# USBdimmer-control.net
KiCad netlist of a schematic drawn in EAGLE
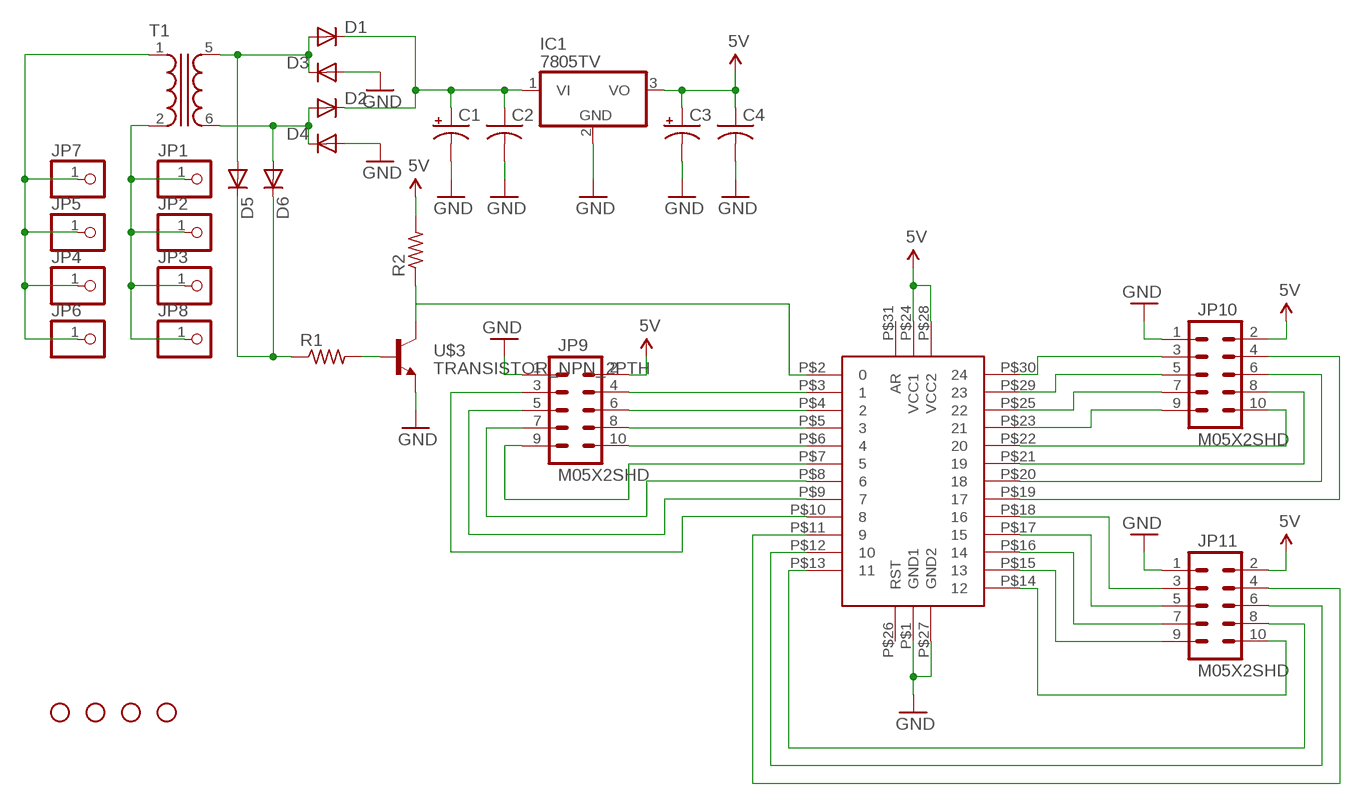
[diagram p0: schematic, sheet 1]

(export (version "E")
  (design (tool "Eeschema 10.0.6"))
  (components
    (comp (ref "C1")
      (value "CPOL-USE3.5-10")
      (footprint "eagle-import:E3,5-10")
      (libsource (lib "eagle-import") (part "CPOL-USE3.5-10"))
    )
    (comp (ref "C2")
      (value "C-US025-030X050")
      (footprint "eagle-import:C025-030X050")
      (libsource (lib "eagle-import") (part "C-US025-030X050"))
    )
    (comp (ref "C3")
      (value "CPOL-USE3.5-10")
      (footprint "eagle-import:E3,5-10")
      (libsource (lib "eagle-import") (part "CPOL-USE3.5-10"))
    )
    (comp (ref "C4")
      (value "C-US025-030X050")
      (footprint "eagle-import:C025-030X050")
      (libsource (lib "eagle-import") (part "C-US025-030X050"))
    )
    (comp (ref "D1")
      (value "DIODEPTH")
      (footprint "eagle-import:DIODE-1N4001")
      (libsource (lib "eagle-import") (part "DIODEPTH"))
    )
    (comp (ref "D2")
      (value "DIODEPTH")
      (footprint "eagle-import:DIODE-1N4001")
      (libsource (lib "eagle-import") (part "DIODEPTH"))
    )
    (comp (ref "D3")
      (value "DIODEPTH")
      (footprint "eagle-import:DIODE-1N4001")
      (libsource (lib "eagle-import") (part "DIODEPTH"))
    )
    (comp (ref "D4")
      (value "DIODEPTH")
      (footprint "eagle-import:DIODE-1N4001")
      (libsource (lib "eagle-import") (part "DIODEPTH"))
    )
    (comp (ref "D5")
      (value "DIODE1N4148")
      (footprint "eagle-import:DIODE-1N4148")
      (libsource (lib "eagle-import") (part "DIODE1N4148"))
    )
    (comp (ref "D6")
      (value "DIODE1N4148")
      (footprint "eagle-import:DIODE-1N4148")
      (libsource (lib "eagle-import") (part "DIODE1N4148"))
    )
    (comp (ref "IC1")
      (value "7805TV")
      (footprint "eagle-import:TO220V")
      (libsource (lib "eagle-import") (part "78TV05"))
    )
    (comp (ref "JP1")
      (value "PINHD-1X1")
      (footprint "eagle-import:1X01")
      (libsource (lib "eagle-import") (part "PINHD-1X1"))
    )
    (comp (ref "JP2")
      (value "PINHD-1X1")
      (footprint "eagle-import:1X01")
      (libsource (lib "eagle-import") (part "PINHD-1X1"))
    )
    (comp (ref "JP3")
      (value "PINHD-1X1")
      (footprint "eagle-import:1X01")
      (libsource (lib "eagle-import") (part "PINHD-1X1"))
    )
    (comp (ref "JP4")
      (value "PINHD-1X1")
      (footprint "eagle-import:1X01")
      (libsource (lib "eagle-import") (part "PINHD-1X1"))
    )
    (comp (ref "JP5")
      (value "PINHD-1X1")
      (footprint "eagle-import:1X01")
      (libsource (lib "eagle-import") (part "PINHD-1X1"))
    )
    (comp (ref "JP6")
      (value "PINHD-1X1")
      (footprint "eagle-import:1X01")
      (libsource (lib "eagle-import") (part "PINHD-1X1"))
    )
    (comp (ref "JP7")
      (value "PINHD-1X1")
      (footprint "eagle-import:1X01")
      (libsource (lib "eagle-import") (part "PINHD-1X1"))
    )
    (comp (ref "JP8")
      (value "PINHD-1X1")
      (footprint "eagle-import:1X01")
      (libsource (lib "eagle-import") (part "PINHD-1X1"))
    )
    (comp (ref "JP9")
      (value "M05X2SHD")
      (footprint "eagle-import:2X5-SHROUDED")
      (libsource (lib "eagle-import") (part "M05X2SHD"))
    )
    (comp (ref "JP10")
      (value "M05X2SHD")
      (footprint "eagle-import:2X5-SHROUDED")
      (libsource (lib "eagle-import") (part "M05X2SHD"))
    )
    (comp (ref "JP11")
      (value "M05X2SHD")
      (footprint "eagle-import:2X5-SHROUDED")
      (libsource (lib "eagle-import") (part "M05X2SHD"))
    )
    (comp (ref "R1")
      (value "FLIPFLOP-RES")
      (footprint "eagle-import:0805-THM")
      (libsource (lib "eagle-import") (part "FLIPFLOP-RES"))
    )
    (comp (ref "R2")
      (value "FLIPFLOP-RES")
      (footprint "eagle-import:0805-THM")
      (libsource (lib "eagle-import") (part "FLIPFLOP-RES"))
    )
    (comp (ref "STANDOFF1")
      (value "STAND-OFF")
      (footprint "eagle-import:STAND-OFF")
      (libsource (lib "eagle-import") (part "STAND-OFF"))
    )
    (comp (ref "STANDOFF2")
      (value "STAND-OFF")
      (footprint "eagle-import:STAND-OFF")
      (libsource (lib "eagle-import") (part "STAND-OFF"))
    )
    (comp (ref "STANDOFF3")
      (value "STAND-OFF")
      (footprint "eagle-import:STAND-OFF")
      (libsource (lib "eagle-import") (part "STAND-OFF"))
    )
    (comp (ref "STANDOFF4")
      (value "STAND-OFF")
      (footprint "eagle-import:STAND-OFF")
      (libsource (lib "eagle-import") (part "STAND-OFF"))
    )
    (comp (ref "T1")
      (value "XFORMER")
      (footprint "eagle-import:T70-E")
      (libsource (lib "eagle-import") (part "XFORMER"))
    )
    (comp (ref "U$1")
      (value "TEENSY2")
      (footprint "eagle-import:TEENSY2")
      (libsource (lib "eagle-import") (part "TEENSY2"))
    )
    (comp (ref "U$3")
      (value "TRANSISTOR_NPN_2PTH")
      (footprint "eagle-import:TO-92")
      (libsource (lib "eagle-import") (part "TRANSISTOR_NPN_2PTH"))
    )
  )
  (nets
    (net (code "1") (name "5V") (class "Default")
      (node (ref "C3") (pin "+") (pinfunction "+_+") (pintype "passive"))
      (node (ref "C4") (pin "1") (pinfunction "1_1") (pintype "passive"))
      (node (ref "IC1") (pin "3") (pinfunction "VO_3") (pintype "passive"))
      (node (ref "JP10") (pin "2") (pinfunction "2_2") (pintype "passive"))
      (node (ref "JP11") (pin "2") (pinfunction "2_2") (pintype "passive"))
      (node (ref "JP9") (pin "2") (pinfunction "2_2") (pintype "passive"))
      (node (ref "R2") (pin "2") (pinfunction "2_2") (pintype "passive"))
      (node (ref "U$1") (pin "P$24") (pinfunction "VCC1_P$24") (pintype "bidirectional"))
      (node (ref "U$1") (pin "P$28") (pinfunction "VCC2_P$28") (pintype "bidirectional"))
    )
    (net (code "2") (name "GND") (class "Default")
      (node (ref "C1") (pin "-") (pinfunction "-_-") (pintype "passive"))
      (node (ref "C2") (pin "2") (pinfunction "2_2") (pintype "passive"))
      (node (ref "C3") (pin "-") (pinfunction "-_-") (pintype "passive"))
      (node (ref "C4") (pin "2") (pinfunction "2_2") (pintype "passive"))
      (node (ref "D3") (pin "A") (pinfunction "A_A") (pintype "passive"))
      (node (ref "D4") (pin "A") (pinfunction "A_A") (pintype "passive"))
      (node (ref "IC1") (pin "2") (pinfunction "GND_2") (pintype "passive"))
      (node (ref "JP10") (pin "1") (pinfunction "1_1") (pintype "passive"))
      (node (ref "JP11") (pin "1") (pinfunction "1_1") (pintype "passive"))
      (node (ref "JP9") (pin "1") (pinfunction "1_1") (pintype "passive"))
      (node (ref "U$1") (pin "P$1") (pinfunction "GND1_P$1") (pintype "bidirectional"))
      (node (ref "U$1") (pin "P$27") (pinfunction "GND2_P$27") (pintype "bidirectional"))
      (node (ref "U$3") (pin "3") (pinfunction "E_3") (pintype "passive"))
    )
    (net (code "3") (name "Net-(D5-PadC)") (class "Default")
      (node (ref "D5") (pin "C") (pinfunction "C_C") (pintype "passive"))
      (node (ref "D6") (pin "C") (pinfunction "C_C") (pintype "passive"))
      (node (ref "R1") (pin "1") (pinfunction "1_1") (pintype "passive"))
    )
    (net (code "4") (name "Net-(IC1-VI)") (class "Default")
      (node (ref "C1") (pin "+") (pinfunction "+_+") (pintype "passive"))
      (node (ref "C2") (pin "1") (pinfunction "1_1") (pintype "passive"))
      (node (ref "D1") (pin "C") (pinfunction "C_C") (pintype "passive"))
      (node (ref "D2") (pin "C") (pinfunction "C_C") (pintype "passive"))
      (node (ref "IC1") (pin "1") (pinfunction "VI_1") (pintype "input"))
    )
    (net (code "5") (name "Net-(T1A-P1)") (class "Default")
      (node (ref "JP4") (pin "1") (pinfunction "1_1") (pintype "passive"))
      (node (ref "JP5") (pin "1") (pinfunction "1_1") (pintype "passive"))
      (node (ref "JP6") (pin "1") (pinfunction "1_1") (pintype "passive"))
      (node (ref "JP7") (pin "1") (pinfunction "1_1") (pintype "passive"))
      (node (ref "T1") (pin "1") (pinfunction "P1_1") (pintype "passive"))
    )
    (net (code "6") (name "Net-(T1A-P2)") (class "Default")
      (node (ref "JP1") (pin "1") (pinfunction "1_1") (pintype "passive"))
      (node (ref "JP2") (pin "1") (pinfunction "1_1") (pintype "passive"))
      (node (ref "JP3") (pin "1") (pinfunction "1_1") (pintype "passive"))
      (node (ref "JP8") (pin "1") (pinfunction "1_1") (pintype "passive"))
      (node (ref "T1") (pin "2") (pinfunction "P2_2") (pintype "passive"))
    )
    (net (code "7") (name "Net-(T1A-S1)") (class "Default")
      (node (ref "D1") (pin "A") (pinfunction "A_A") (pintype "passive"))
      (node (ref "D3") (pin "C") (pinfunction "C_C") (pintype "passive"))
      (node (ref "D5") (pin "A") (pinfunction "A_A") (pintype "passive"))
      (node (ref "T1") (pin "5") (pinfunction "S1_5") (pintype "passive"))
    )
    (net (code "8") (name "Net-(T1A-S2)") (class "Default")
      (node (ref "D2") (pin "A") (pinfunction "A_A") (pintype "passive"))
      (node (ref "D4") (pin "C") (pinfunction "C_C") (pintype "passive"))
      (node (ref "D6") (pin "A") (pinfunction "A_A") (pintype "passive"))
      (node (ref "T1") (pin "6") (pinfunction "S2_6") (pintype "passive"))
    )
    (net (code "9") (name "Net-(U$1-0)") (class "Default")
      (node (ref "R2") (pin "1") (pinfunction "1_1") (pintype "passive"))
      (node (ref "U$1") (pin "P$2") (pinfunction "0_P$2") (pintype "bidirectional"))
      (node (ref "U$3") (pin "1") (pinfunction "C_1") (pintype "passive"))
    )
    (net (code "10") (name "Net-(U$1-1)") (class "Default")
      (node (ref "JP9") (pin "4") (pinfunction "4_4") (pintype "passive"))
      (node (ref "U$1") (pin "P$3") (pinfunction "1_P$3") (pintype "bidirectional"))
    )
    (net (code "11") (name "Net-(U$1-2)") (class "Default")
      (node (ref "JP9") (pin "6") (pinfunction "6_6") (pintype "passive"))
      (node (ref "U$1") (pin "P$4") (pinfunction "2_P$4") (pintype "bidirectional"))
    )
    (net (code "12") (name "Net-(U$1-3)") (class "Default")
      (node (ref "JP9") (pin "8") (pinfunction "8_8") (pintype "passive"))
      (node (ref "U$1") (pin "P$5") (pinfunction "3_P$5") (pintype "bidirectional"))
    )
    (net (code "13") (name "Net-(U$1-4)") (class "Default")
      (node (ref "JP9") (pin "10") (pinfunction "10_10") (pintype "passive"))
      (node (ref "U$1") (pin "P$6") (pinfunction "4_P$6") (pintype "bidirectional"))
    )
    (net (code "14") (name "Net-(U$1-5)") (class "Default")
      (node (ref "JP9") (pin "9") (pinfunction "9_9") (pintype "passive"))
      (node (ref "U$1") (pin "P$7") (pinfunction "5_P$7") (pintype "bidirectional"))
    )
    (net (code "15") (name "Net-(U$1-6)") (class "Default")
      (node (ref "JP9") (pin "7") (pinfunction "7_7") (pintype "passive"))
      (node (ref "U$1") (pin "P$8") (pinfunction "6_P$8") (pintype "bidirectional"))
    )
    (net (code "16") (name "Net-(U$1-7)") (class "Default")
      (node (ref "JP9") (pin "5") (pinfunction "5_5") (pintype "passive"))
      (node (ref "U$1") (pin "P$9") (pinfunction "7_P$9") (pintype "bidirectional"))
    )
    (net (code "17") (name "Net-(U$1-8)") (class "Default")
      (node (ref "JP9") (pin "3") (pinfunction "3_3") (pintype "passive"))
      (node (ref "U$1") (pin "P$10") (pinfunction "8_P$10") (pintype "bidirectional"))
    )
    (net (code "18") (name "Net-(U$1-9)") (class "Default")
      (node (ref "JP11") (pin "4") (pinfunction "4_4") (pintype "passive"))
      (node (ref "U$1") (pin "P$11") (pinfunction "9_P$11") (pintype "bidirectional"))
    )
    (net (code "19") (name "Net-(U$1-10)") (class "Default")
      (node (ref "JP11") (pin "6") (pinfunction "6_6") (pintype "passive"))
      (node (ref "U$1") (pin "P$12") (pinfunction "10_P$12") (pintype "bidirectional"))
    )
    (net (code "20") (name "Net-(U$1-11)") (class "Default")
      (node (ref "JP11") (pin "8") (pinfunction "8_8") (pintype "passive"))
      (node (ref "U$1") (pin "P$13") (pinfunction "11_P$13") (pintype "bidirectional"))
    )
    (net (code "21") (name "Net-(U$1-12)") (class "Default")
      (node (ref "JP11") (pin "10") (pinfunction "10_10") (pintype "passive"))
      (node (ref "U$1") (pin "P$14") (pinfunction "12_P$14") (pintype "bidirectional"))
    )
    (net (code "22") (name "Net-(U$1-13)") (class "Default")
      (node (ref "JP11") (pin "9") (pinfunction "9_9") (pintype "passive"))
      (node (ref "U$1") (pin "P$15") (pinfunction "13_P$15") (pintype "bidirectional"))
    )
    (net (code "23") (name "Net-(U$1-14)") (class "Default")
      (node (ref "JP11") (pin "7") (pinfunction "7_7") (pintype "passive"))
      (node (ref "U$1") (pin "P$16") (pinfunction "14_P$16") (pintype "bidirectional"))
    )
    (net (code "24") (name "Net-(U$1-15)") (class "Default")
      (node (ref "JP11") (pin "5") (pinfunction "5_5") (pintype "passive"))
      (node (ref "U$1") (pin "P$17") (pinfunction "15_P$17") (pintype "bidirectional"))
    )
    (net (code "25") (name "Net-(U$1-16)") (class "Default")
      (node (ref "JP11") (pin "3") (pinfunction "3_3") (pintype "passive"))
      (node (ref "U$1") (pin "P$18") (pinfunction "16_P$18") (pintype "bidirectional"))
    )
    (net (code "26") (name "Net-(U$1-17)") (class "Default")
      (node (ref "JP10") (pin "4") (pinfunction "4_4") (pintype "passive"))
      (node (ref "U$1") (pin "P$19") (pinfunction "17_P$19") (pintype "bidirectional"))
    )
    (net (code "27") (name "Net-(U$1-18)") (class "Default")
      (node (ref "JP10") (pin "6") (pinfunction "6_6") (pintype "passive"))
      (node (ref "U$1") (pin "P$20") (pinfunction "18_P$20") (pintype "bidirectional"))
    )
    (net (code "28") (name "Net-(U$1-19)") (class "Default")
      (node (ref "JP10") (pin "8") (pinfunction "8_8") (pintype "passive"))
      (node (ref "U$1") (pin "P$21") (pinfunction "19_P$21") (pintype "bidirectional"))
    )
    (net (code "29") (name "Net-(U$1-20)") (class "Default")
      (node (ref "JP10") (pin "10") (pinfunction "10_10") (pintype "passive"))
      (node (ref "U$1") (pin "P$22") (pinfunction "20_P$22") (pintype "bidirectional"))
    )
    (net (code "30") (name "Net-(U$1-21)") (class "Default")
      (node (ref "JP10") (pin "9") (pinfunction "9_9") (pintype "passive"))
      (node (ref "U$1") (pin "P$23") (pinfunction "21_P$23") (pintype "bidirectional"))
    )
    (net (code "31") (name "Net-(U$1-22)") (class "Default")
      (node (ref "JP10") (pin "7") (pinfunction "7_7") (pintype "passive"))
      (node (ref "U$1") (pin "P$25") (pinfunction "22_P$25") (pintype "bidirectional"))
    )
    (net (code "32") (name "Net-(U$1-23)") (class "Default")
      (node (ref "JP10") (pin "5") (pinfunction "5_5") (pintype "passive"))
      (node (ref "U$1") (pin "P$29") (pinfunction "23_P$29") (pintype "bidirectional"))
    )
    (net (code "33") (name "Net-(U$1-24)") (class "Default")
      (node (ref "JP10") (pin "3") (pinfunction "3_3") (pintype "passive"))
      (node (ref "U$1") (pin "P$30") (pinfunction "24_P$30") (pintype "bidirectional"))
    )
    (net (code "34") (name "Net-(U$3-B)") (class "Default")
      (node (ref "R1") (pin "2") (pinfunction "2_2") (pintype "passive"))
      (node (ref "U$3") (pin "2") (pinfunction "B_2") (pintype "passive"))
    )
    (net (code "35") (name "unconnected-(U$1-AR-PadP$31)") (class "Default")
      (node (ref "U$1") (pin "P$31") (pinfunction "AR_P$31") (pintype "bidirectional"))
    )
    (net (code "36") (name "unconnected-(U$1-RST-PadP$26)") (class "Default")
      (node (ref "U$1") (pin "P$26") (pinfunction "RST_P$26") (pintype "bidirectional"))
    )
  )
)
